# LEO_COTS_no_siggen_rev0.net
KiCad netlist of a schematic drawn in Altium Designer
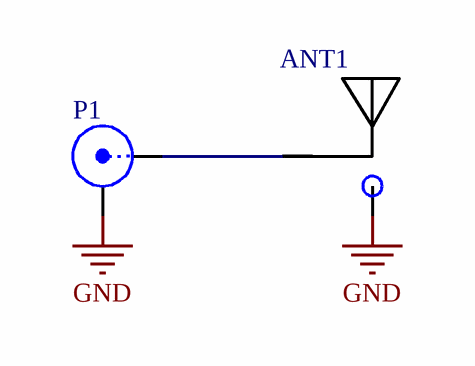
[diagram p0: LEO_COTS_no_siggen_rev0.SchDoc]

(export (version "E")
  (design (tool "Eeschema 10.0.6"))
  (components
    (comp (ref "ANT1")
      (value "ANT")
      (footprint "RESLOOP_OD10_fw15_fl180_sw12_sl15")
      (description "PCB antenna")
      (libsource (lib "LEO_COTS_components") (part "ANT"))
    )
    (comp (ref "P1")
      (value "1909763-1")
      (footprint "1909763-1")
      (description "CONN UMCC JACK STR 50OHM SMD")
      (libsource (lib "LEO_COTS_components") (part "1909763-1"))
    )
  )
  (nets
    (net (code "1") (name "GND") (class "Default")
      (node (ref "ANT1") (pin "2") (pinfunction "-_2") (pintype "passive"))
      (node (ref "P1") (pin "2") (pinfunction "Y_2") (pintype "passive"))
    )
    (net (code "2") (name "Net-(ANT1-+)") (class "Default")
      (node (ref "ANT1") (pin "1") (pinfunction "+_1") (pintype "passive"))
      (node (ref "P1") (pin "1") (pinfunction "X_1") (pintype "passive"))
    )
  )
)
